# untitled.net
KiCad netlist of a schematic drawn in EAGLE
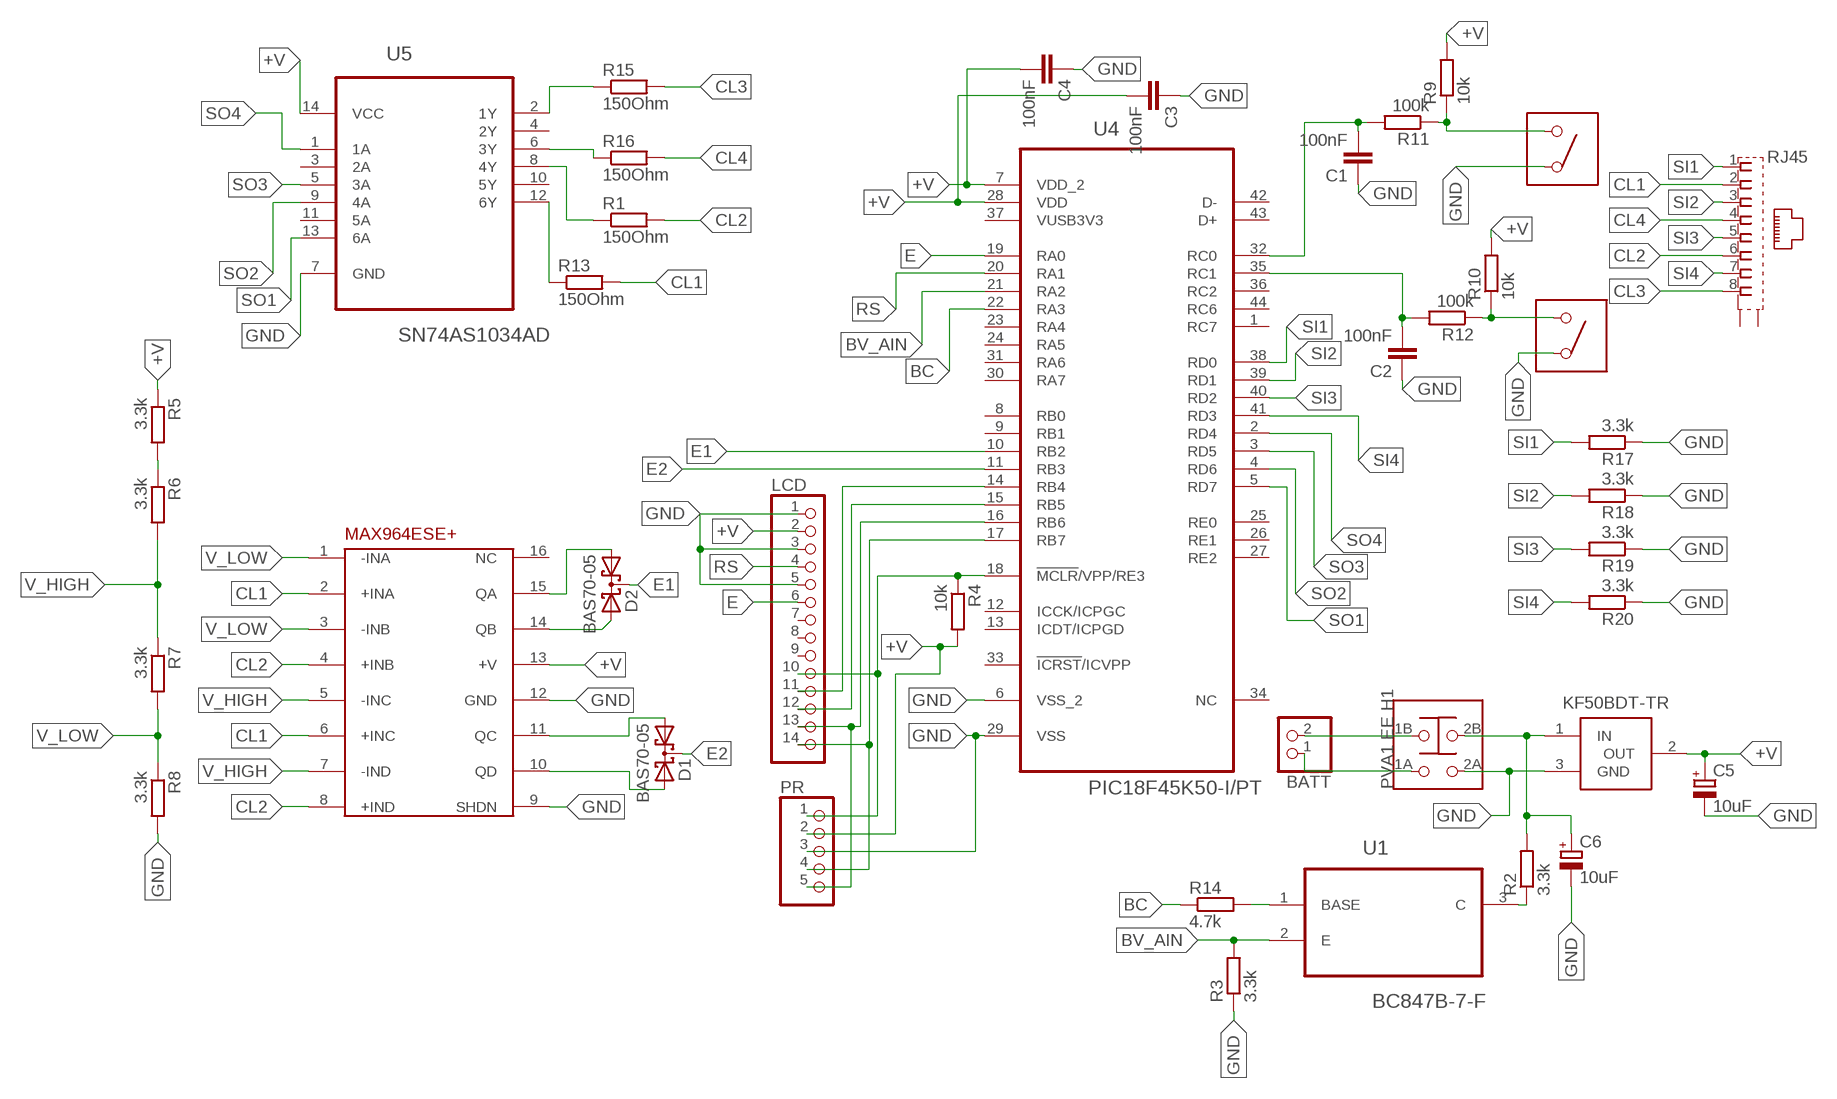
[diagram p0: schematic, sheet 1]

(export (version "E")
  (design (tool "Eeschema 10.0.6"))
  (components
    (comp (ref "BATT")
      (value "PINHD-1X2")
      (footprint "eagle-import:1X02")
      (libsource (lib "eagle-import") (part "PINHD-1X2"))
    )
    (comp (ref "C1")
      (value "100nF")
      (footprint "eagle-import:C0603")
      (fields (field (name "MF") "YAGEO (PHYCOMP)") (field (name "MPN") "CC0603KRX7R7BB104"))
      (libsource (lib "eagle-import") (part "C-EUC0603"))
    )
    (comp (ref "C2")
      (value "100nF")
      (footprint "eagle-import:C0603")
      (fields (field (name "MF") "YAGEO (PHYCOMP)") (field (name "MPN") "CC0603KRX7R7BB104"))
      (libsource (lib "eagle-import") (part "C-EUC0603"))
    )
    (comp (ref "C3")
      (value "100nF")
      (footprint "eagle-import:C0603")
      (fields (field (name "MF") "YAGEO (PHYCOMP)") (field (name "MPN") "CC0603KRX7R7BB104"))
      (libsource (lib "eagle-import") (part "C-EUC0603"))
    )
    (comp (ref "C4")
      (value "100nF")
      (footprint "eagle-import:C0603")
      (fields (field (name "MF") "YAGEO (PHYCOMP)") (field (name "MPN") "CC0603KRX7R7BB104"))
      (libsource (lib "eagle-import") (part "C-EUC0603"))
    )
    (comp (ref "C5")
      (value "10uF")
      (footprint "eagle-import:153CLV-0405")
      (fields (field (name "MF") "RUBYCON") (field (name "MPN") "16TZV10M4X6.1"))
      (libsource (lib "eagle-import") (part "CPOL-EU153CLV-0405"))
    )
    (comp (ref "C6")
      (value "10uF")
      (footprint "eagle-import:153CLV-0405")
      (fields (field (name "MF") "RUBYCON") (field (name "MPN") "16TZV10M4X6.1"))
      (libsource (lib "eagle-import") (part "CPOL-EU153CLV-0405"))
    )
    (comp (ref "D1")
      (value "BAS70-05")
      (footprint "eagle-import:SOT23")
      (libsource (lib "eagle-import") (part "BAS70-05"))
    )
    (comp (ref "D2")
      (value "BAS70-05")
      (footprint "eagle-import:SOT23")
      (libsource (lib "eagle-import") (part "BAS70-05"))
    )
    (comp (ref "LCD")
      (value "PINHD-1X14")
      (footprint "eagle-import:1X14")
      (libsource (lib "eagle-import") (part "PINHD-1X14"))
    )
    (comp (ref "PR")
      (value "PINHD-1X5")
      (footprint "eagle-import:1X05")
      (libsource (lib "eagle-import") (part "PINHD-1X5"))
    )
    (comp (ref "R1")
      (value "150Ohm")
      (footprint "eagle-import:R0603")
      (fields (field (name "MF") "TE CONNECTIVITY / NEOHM") (field (name "MPN") "CPF0603F150RC1"))
      (libsource (lib "eagle-import") (part "R-EU_R0603"))
    )
    (comp (ref "R2")
      (value "3.3k")
      (footprint "eagle-import:R0603")
      (fields (field (name "MF") "TE CONNECTIVITY") (field (name "MPN") "CRGH0603F3K3"))
      (libsource (lib "eagle-import") (part "R-EU_R0603"))
    )
    (comp (ref "R3")
      (value "3.3k")
      (footprint "eagle-import:R0603")
      (fields (field (name "MF") "TE CONNECTIVITY") (field (name "MPN") "CRGH0603F3K3"))
      (libsource (lib "eagle-import") (part "R-EU_R0603"))
    )
    (comp (ref "R4")
      (value "10k")
      (footprint "eagle-import:R0603")
      (fields (field (name "MF") "VISHAY") (field (name "MPN") "CRCW060310K0FKTA"))
      (libsource (lib "eagle-import") (part "R-EU_R0603"))
    )
    (comp (ref "R5")
      (value "3.3k")
      (footprint "eagle-import:R0603")
      (fields (field (name "MF") "TE CONNECTIVITY") (field (name "MPN") "CRGH0603F3K3"))
      (libsource (lib "eagle-import") (part "R-EU_R0603"))
    )
    (comp (ref "R6")
      (value "3.3k")
      (footprint "eagle-import:R0603")
      (fields (field (name "MF") "TE CONNECTIVITY") (field (name "MPN") "CRGH0603F3K3"))
      (libsource (lib "eagle-import") (part "R-EU_R0603"))
    )
    (comp (ref "R7")
      (value "3.3k")
      (footprint "eagle-import:R0603")
      (fields (field (name "MF") "TE CONNECTIVITY") (field (name "MPN") "CRGH0603F3K3"))
      (libsource (lib "eagle-import") (part "R-EU_R0603"))
    )
    (comp (ref "R8")
      (value "3.3k")
      (footprint "eagle-import:R0603")
      (fields (field (name "MF") "TE CONNECTIVITY") (field (name "MPN") "CRGH0603F3K3"))
      (libsource (lib "eagle-import") (part "R-EU_R0603"))
    )
    (comp (ref "R9")
      (value "10k")
      (footprint "eagle-import:R0603")
      (fields (field (name "MF") "VISHAY") (field (name "MPN") "CRCW060310K0FKTA"))
      (libsource (lib "eagle-import") (part "R-EU_R0603"))
    )
    (comp (ref "R10")
      (value "10k")
      (footprint "eagle-import:R0603")
      (fields (field (name "MF") "VISHAY") (field (name "MPN") "CRCW060310K0FKTA"))
      (libsource (lib "eagle-import") (part "R-EU_R0603"))
    )
    (comp (ref "R11")
      (value "100k")
      (footprint "eagle-import:R0603")
      (fields (field (name "MF") "TE CONNECTIVITY") (field (name "MPN") "CRGH0603J100K"))
      (libsource (lib "eagle-import") (part "R-EU_R0603"))
    )
    (comp (ref "R12")
      (value "100k")
      (footprint "eagle-import:R0603")
      (fields (field (name "MF") "TE CONNECTIVITY") (field (name "MPN") "CRGH0603J100K"))
      (libsource (lib "eagle-import") (part "R-EU_R0603"))
    )
    (comp (ref "R13")
      (value "150Ohm")
      (footprint "eagle-import:R0603")
      (fields (field (name "MF") "TE CONNECTIVITY / NEOHM") (field (name "MPN") "CPF0603F150RC1"))
      (libsource (lib "eagle-import") (part "R-EU_R0603"))
    )
    (comp (ref "R14")
      (value "4.7k")
      (footprint "eagle-import:R0603")
      (fields (field (name "MF") "VISHAY") (field (name "MPN") "CRCW06034K70FKEA"))
      (libsource (lib "eagle-import") (part "R-EU_R0603"))
    )
    (comp (ref "R15")
      (value "150Ohm")
      (footprint "eagle-import:R0603")
      (fields (field (name "MF") "TE CONNECTIVITY / NEOHM") (field (name "MPN") "CPF0603F150RC1"))
      (libsource (lib "eagle-import") (part "R-EU_R0603"))
    )
    (comp (ref "R16")
      (value "150Ohm")
      (footprint "eagle-import:R0603")
      (fields (field (name "MF") "TE CONNECTIVITY / NEOHM") (field (name "MPN") "CPF0603F150RC1"))
      (libsource (lib "eagle-import") (part "R-EU_R0603"))
    )
    (comp (ref "R17")
      (value "3.3k")
      (footprint "eagle-import:R0603")
      (fields (field (name "MF") "TE CONNECTIVITY") (field (name "MPN") "CRGH0603F3K3"))
      (libsource (lib "eagle-import") (part "R-EU_R0603"))
    )
    (comp (ref "R18")
      (value "3.3k")
      (footprint "eagle-import:R0603")
      (fields (field (name "MF") "TE CONNECTIVITY") (field (name "MPN") "CRGH0603F3K3"))
      (libsource (lib "eagle-import") (part "R-EU_R0603"))
    )
    (comp (ref "R19")
      (value "3.3k")
      (footprint "eagle-import:R0603")
      (fields (field (name "MF") "TE CONNECTIVITY") (field (name "MPN") "CRGH0603F3K3"))
      (libsource (lib "eagle-import") (part "R-EU_R0603"))
    )
    (comp (ref "R20")
      (value "3.3k")
      (footprint "eagle-import:R0603")
      (fields (field (name "MF") "TE CONNECTIVITY") (field (name "MPN") "CRGH0603F3K3"))
      (libsource (lib "eagle-import") (part "R-EU_R0603"))
    )
    (comp (ref "RJ45")
      (value "1-406541-6")
      (footprint "eagle-import:RJ45")
      (fields (field (name "MF") "TE CONNECTIVITY / AMP") (field (name "MF_1") "AMP - TE CONNECTIVITY"))
      (libsource (lib "eagle-import") (part "1-406541-6"))
    )
    (comp (ref "U$1")
      (value "KF50BDT-TR")
      (footprint "eagle-import:TO252")
      (fields (field (name "MF") "STMICROELECTRONICS"))
      (libsource (lib "eagle-import") (part "KF50BDT-TR"))
    )
    (comp (ref "U$2")
      (value "MAX964ESE+")
      (footprint "eagle-import:SO16")
      (fields
        (field (name "MF") "MAXIM INTEGRATED PRODUCTS")
        (field (name "MPN") "MAX9201ESE+")
        (field (name "MPN_1") "MAX964ESE+")
        (field (name "OC_FARNELL") "2518928")
      )
      (libsource (lib "eagle-import") (part "MAX964ESE+"))
    )
    (comp (ref "U$3")
      (value "PVA1_EE_H1")
      (footprint "eagle-import:PVA1_EE_H1")
      (fields (field (name "MF") "C & K COMPONENTS") (field (name "MPN") "PVA1 EE H1 3.5N V2"))
      (libsource (lib "eagle-import") (part "PVA1_EE_H1"))
    )
    (comp (ref "U$4")
      (value "FSM4JRT")
      (footprint "eagle-import:FSM4JRT")
      (fields
        (field (name "MPN") "TE CONNECTIVITY / ALCOSWITCH")
        (field (name "MF") "TE CONNECTIVITY / ALCOSWITCH")
        (field (name "MPN_1") "FSM4JRT")
      )
      (libsource (lib "eagle-import") (part "FSM4JRT"))
    )
    (comp (ref "U$5")
      (value "FSM4JRT")
      (footprint "eagle-import:FSM4JRT")
      (fields
        (field (name "MPN") "TE CONNECTIVITY / ALCOSWITCH")
        (field (name "MF") "TE CONNECTIVITY / ALCOSWITCH")
        (field (name "MPN_1") "FSM4JRT")
      )
      (libsource (lib "eagle-import") (part "FSM4JRT"))
    )
    (comp (ref "U1")
      (value "BC847B-7-F")
      (footprint "eagle-import:SOT95P240X110-3N")
      (fields (field (name "MF") "DIODES INC."))
      (libsource (lib "eagle-import") (part "BC847B-7-F"))
    )
    (comp (ref "U4")
      (value "PIC18F45K50-I/PT")
      (footprint "eagle-import:TQFP80P1200X1200X120-44N")
      (fields (field (name "MF") "MICROCHIP"))
      (libsource (lib "eagle-import") (part "PIC18F45K50-I/PT"))
    )
    (comp (ref "U5")
      (value "SN74AS1034AD")
      (footprint "eagle-import:SOIC127P600X175-14N")
      (fields (field (name "MF") "TEXAS INSTRUMENTS"))
      (libsource (lib "eagle-import") (part "SN74AS1034AD"))
    )
  )
  (nets
    (net (code "1") (name "+V") (class "Default")
      (node (ref "C3") (pin "2") (pinfunction "2_2") (pintype "passive"))
      (node (ref "C4") (pin "2") (pinfunction "2_2") (pintype "passive"))
      (node (ref "C5") (pin "+") (pinfunction "+_+") (pintype "passive"))
      (node (ref "LCD") (pin "2") (pinfunction "2_2") (pintype "passive"))
      (node (ref "PR") (pin "2") (pinfunction "2_2") (pintype "passive"))
      (node (ref "R10") (pin "2") (pinfunction "2_2") (pintype "passive"))
      (node (ref "R4") (pin "2") (pinfunction "2_2") (pintype "passive"))
      (node (ref "R5") (pin "1") (pinfunction "1_1") (pintype "passive"))
      (node (ref "R9") (pin "2") (pinfunction "2_2") (pintype "passive"))
      (node (ref "U$1") (pin "2") (pinfunction "OUT_2") (pintype "output"))
      (node (ref "U$2") (pin "13") (pinfunction "+V_13") (pintype "power_in"))
      (node (ref "U4") (pin "28") (pinfunction "VDD_28") (pintype "power_in"))
      (node (ref "U4") (pin "7") (pinfunction "VDD_2_7") (pintype "power_in"))
      (node (ref "U5") (pin "14") (pinfunction "VCC_14") (pintype "power_in"))
    )
    (net (code "2") (name "/VUSB3V3") (class "Default")
      (node (ref "U4") (pin "37") (pinfunction "VUSB3V3_37") (pintype "power_in"))
    )
    (net (code "3") (name "BC") (class "Default")
      (node (ref "R14") (pin "1") (pinfunction "1_1") (pintype "passive"))
      (node (ref "U4") (pin "22") (pinfunction "RA3_22") (pintype "bidirectional"))
    )
    (net (code "4") (name "BV_AIN") (class "Default")
      (node (ref "R3") (pin "2") (pinfunction "2_2") (pintype "passive"))
      (node (ref "U1") (pin "2") (pinfunction "E_2") (pintype "passive"))
      (node (ref "U4") (pin "21") (pinfunction "RA2_21") (pintype "bidirectional"))
    )
    (net (code "5") (name "CL1") (class "Default")
      (node (ref "R13") (pin "2") (pinfunction "2_2") (pintype "passive"))
      (node (ref "RJ45") (pin "2") (pinfunction "2_2") (pintype "passive"))
      (node (ref "U$2") (pin "2") (pinfunction "+INA_2") (pintype "input"))
      (node (ref "U$2") (pin "6") (pinfunction "+INC_6") (pintype "input"))
    )
    (net (code "6") (name "CL2") (class "Default")
      (node (ref "R1") (pin "2") (pinfunction "2_2") (pintype "passive"))
      (node (ref "RJ45") (pin "6") (pinfunction "6_6") (pintype "passive"))
      (node (ref "U$2") (pin "4") (pinfunction "+INB_4") (pintype "input"))
      (node (ref "U$2") (pin "8") (pinfunction "+IND_8") (pintype "input"))
    )
    (net (code "7") (name "CL3") (class "Default")
      (node (ref "R15") (pin "2") (pinfunction "2_2") (pintype "passive"))
      (node (ref "RJ45") (pin "8") (pinfunction "8_8") (pintype "passive"))
    )
    (net (code "8") (name "CL4") (class "Default")
      (node (ref "R16") (pin "2") (pinfunction "2_2") (pintype "passive"))
      (node (ref "RJ45") (pin "4") (pinfunction "4_4") (pintype "passive"))
    )
    (net (code "9") (name "E") (class "Default")
      (node (ref "LCD") (pin "6") (pinfunction "6_6") (pintype "passive"))
      (node (ref "U4") (pin "19") (pinfunction "RA0_19") (pintype "bidirectional"))
    )
    (net (code "10") (name "E1") (class "Default")
      (node (ref "D2") (pin "3") (pinfunction "C_3") (pintype "passive"))
      (node (ref "U4") (pin "10") (pinfunction "RB2_10") (pintype "bidirectional"))
    )
    (net (code "11") (name "E2") (class "Default")
      (node (ref "D1") (pin "3") (pinfunction "C_3") (pintype "passive"))
      (node (ref "U4") (pin "11") (pinfunction "RB3_11") (pintype "bidirectional"))
    )
    (net (code "12") (name "GND") (class "Default")
      (node (ref "C1") (pin "1") (pinfunction "1_1") (pintype "passive"))
      (node (ref "C2") (pin "1") (pinfunction "1_1") (pintype "passive"))
      (node (ref "C3") (pin "1") (pinfunction "1_1") (pintype "passive"))
      (node (ref "C4") (pin "1") (pinfunction "1_1") (pintype "passive"))
      (node (ref "C5") (pin "-") (pinfunction "-_-") (pintype "passive"))
      (node (ref "C6") (pin "-") (pinfunction "-_-") (pintype "passive"))
      (node (ref "LCD") (pin "1") (pinfunction "1_1") (pintype "passive"))
      (node (ref "LCD") (pin "3") (pinfunction "3_3") (pintype "passive"))
      (node (ref "LCD") (pin "5") (pinfunction "5_5") (pintype "passive"))
      (node (ref "PR") (pin "3") (pinfunction "3_3") (pintype "passive"))
      (node (ref "R17") (pin "1") (pinfunction "1_1") (pintype "passive"))
      (node (ref "R18") (pin "1") (pinfunction "1_1") (pintype "passive"))
      (node (ref "R19") (pin "1") (pinfunction "1_1") (pintype "passive"))
      (node (ref "R20") (pin "1") (pinfunction "1_1") (pintype "passive"))
      (node (ref "R3") (pin "1") (pinfunction "1_1") (pintype "passive"))
      (node (ref "R8") (pin "2") (pinfunction "2_2") (pintype "passive"))
      (node (ref "U$1") (pin "3") (pinfunction "GND_3") (pintype "output"))
      (node (ref "U$2") (pin "12") (pinfunction "GND_12") (pintype "power_in"))
      (node (ref "U$2") (pin "9") (pinfunction "SHDN_9") (pintype "input"))
      (node (ref "U$3") (pin "2A") (pinfunction "2A_2A") (pintype "bidirectional"))
      (node (ref "U$4") (pin "2") (pinfunction "2_2") (pintype "passive"))
      (node (ref "U$5") (pin "2") (pinfunction "2_2") (pintype "passive"))
      (node (ref "U4") (pin "29") (pinfunction "VSS_29") (pintype "power_in"))
      (node (ref "U4") (pin "6") (pinfunction "VSS_2_6") (pintype "power_in"))
      (node (ref "U5") (pin "7") (pinfunction "GND_7") (pintype "passive"))
    )
    (net (code "13") (name "Net-(BATT-Pad1)") (class "Default")
      (node (ref "BATT") (pin "1") (pinfunction "1_1") (pintype "passive"))
      (node (ref "U$3") (pin "1A") (pinfunction "1A_1A") (pintype "bidirectional"))
    )
    (net (code "14") (name "Net-(BATT-Pad2)") (class "Default")
      (node (ref "BATT") (pin "2") (pinfunction "2_2") (pintype "passive"))
      (node (ref "U$3") (pin "1B") (pinfunction "1B_1B") (pintype "bidirectional"))
    )
    (net (code "15") (name "Net-(D1-A1)") (class "Default")
      (node (ref "D1") (pin "1") (pinfunction "A1_1") (pintype "passive"))
      (node (ref "U$2") (pin "11") (pinfunction "QC_11") (pintype "output"))
    )
    (net (code "16") (name "Net-(D1-A2)") (class "Default")
      (node (ref "D1") (pin "2") (pinfunction "A2_2") (pintype "passive"))
      (node (ref "U$2") (pin "10") (pinfunction "QD_10") (pintype "output"))
    )
    (net (code "17") (name "Net-(D2-A1)") (class "Default")
      (node (ref "D2") (pin "1") (pinfunction "A1_1") (pintype "passive"))
      (node (ref "U$2") (pin "15") (pinfunction "QA_15") (pintype "output"))
    )
    (net (code "18") (name "Net-(D2-A2)") (class "Default")
      (node (ref "D2") (pin "2") (pinfunction "A2_2") (pintype "passive"))
      (node (ref "U$2") (pin "14") (pinfunction "QB_14") (pintype "output"))
    )
    (net (code "19") (name "Net-(R5-Pad2)") (class "Default")
      (node (ref "R5") (pin "2") (pinfunction "2_2") (pintype "passive"))
      (node (ref "R6") (pin "1") (pinfunction "1_1") (pintype "passive"))
    )
    (net (code "20") (name "Net-(R10-Pad1)") (class "Default")
      (node (ref "R10") (pin "1") (pinfunction "1_1") (pintype "passive"))
      (node (ref "R12") (pin "1") (pinfunction "1_1") (pintype "passive"))
      (node (ref "U$5") (pin "1") (pinfunction "1_1") (pintype "passive"))
    )
    (net (code "21") (name "Net-(R11-Pad1)") (class "Default")
      (node (ref "R11") (pin "1") (pinfunction "1_1") (pintype "passive"))
      (node (ref "R9") (pin "1") (pinfunction "1_1") (pintype "passive"))
      (node (ref "U$4") (pin "1") (pinfunction "1_1") (pintype "passive"))
    )
    (net (code "22") (name "Net-(U$1-IN)") (class "Default")
      (node (ref "C6") (pin "+") (pinfunction "+_+") (pintype "passive"))
      (node (ref "R2") (pin "2") (pinfunction "2_2") (pintype "passive"))
      (node (ref "U$1") (pin "1") (pinfunction "IN_1") (pintype "input"))
      (node (ref "U$3") (pin "2B") (pinfunction "2B_2B") (pintype "bidirectional"))
    )
    (net (code "23") (name "Net-(U1-BASE)") (class "Default")
      (node (ref "R14") (pin "2") (pinfunction "2_2") (pintype "passive"))
      (node (ref "U1") (pin "1") (pinfunction "BASE_1") (pintype "passive"))
    )
    (net (code "24") (name "Net-(U1-C)") (class "Default")
      (node (ref "R2") (pin "1") (pinfunction "1_1") (pintype "passive"))
      (node (ref "U1") (pin "3") (pinfunction "C_3") (pintype "passive"))
    )
    (net (code "25") (name "Net-(U4-RB4)") (class "Default")
      (node (ref "LCD") (pin "11") (pinfunction "11_11") (pintype "passive"))
      (node (ref "U4") (pin "14") (pinfunction "RB4_14") (pintype "bidirectional"))
    )
    (net (code "26") (name "Net-(U4-RB5)") (class "Default")
      (node (ref "LCD") (pin "12") (pinfunction "12_12") (pintype "passive"))
      (node (ref "U4") (pin "15") (pinfunction "RB5_15") (pintype "bidirectional"))
    )
    (net (code "27") (name "Net-(U4-RB6)") (class "Default")
      (node (ref "LCD") (pin "13") (pinfunction "13_13") (pintype "passive"))
      (node (ref "PR") (pin "5") (pinfunction "5_5") (pintype "passive"))
      (node (ref "U4") (pin "16") (pinfunction "RB6_16") (pintype "bidirectional"))
    )
    (net (code "28") (name "Net-(U4-RB7)") (class "Default")
      (node (ref "LCD") (pin "14") (pinfunction "14_14") (pintype "passive"))
      (node (ref "PR") (pin "4") (pinfunction "4_4") (pintype "passive"))
      (node (ref "U4") (pin "17") (pinfunction "RB7_17") (pintype "bidirectional"))
    )
    (net (code "29") (name "Net-(U4-RC0)") (class "Default")
      (node (ref "C1") (pin "2") (pinfunction "2_2") (pintype "passive"))
      (node (ref "R11") (pin "2") (pinfunction "2_2") (pintype "passive"))
      (node (ref "U4") (pin "32") (pinfunction "RC0_32") (pintype "bidirectional"))
    )
    (net (code "30") (name "Net-(U4-RC1)") (class "Default")
      (node (ref "C2") (pin "2") (pinfunction "2_2") (pintype "passive"))
      (node (ref "R12") (pin "2") (pinfunction "2_2") (pintype "passive"))
      (node (ref "U4") (pin "35") (pinfunction "RC1_35") (pintype "bidirectional"))
    )
    (net (code "31") (name "Net-(U4-~{MCLR}{slash}VPP{slash}RE3)") (class "Default")
      (node (ref "LCD") (pin "10") (pinfunction "10_10") (pintype "passive"))
      (node (ref "PR") (pin "1") (pinfunction "1_1") (pintype "passive"))
      (node (ref "R4") (pin "1") (pinfunction "1_1") (pintype "passive"))
      (node (ref "U4") (pin "18") (pinfunction "~{MCLR}/VPP/RE3_18") (pintype "input"))
    )
    (net (code "32") (name "Net-(U5-1Y)") (class "Default")
      (node (ref "R15") (pin "1") (pinfunction "1_1") (pintype "passive"))
      (node (ref "U5") (pin "2") (pinfunction "1Y_2") (pintype "output"))
    )
    (net (code "33") (name "Net-(U5-3Y)") (class "Default")
      (node (ref "R16") (pin "1") (pinfunction "1_1") (pintype "passive"))
      (node (ref "U5") (pin "6") (pinfunction "3Y_6") (pintype "output"))
    )
    (net (code "34") (name "Net-(U5-4Y)") (class "Default")
      (node (ref "R1") (pin "1") (pinfunction "1_1") (pintype "passive"))
      (node (ref "U5") (pin "8") (pinfunction "4Y_8") (pintype "output"))
    )
    (net (code "35") (name "Net-(U5-6Y)") (class "Default")
      (node (ref "R13") (pin "1") (pinfunction "1_1") (pintype "passive"))
      (node (ref "U5") (pin "12") (pinfunction "6Y_12") (pintype "output"))
    )
    (net (code "36") (name "RS") (class "Default")
      (node (ref "LCD") (pin "4") (pinfunction "4_4") (pintype "passive"))
      (node (ref "U4") (pin "20") (pinfunction "RA1_20") (pintype "bidirectional"))
    )
    (net (code "37") (name "SI1") (class "Default")
      (node (ref "R17") (pin "2") (pinfunction "2_2") (pintype "passive"))
      (node (ref "RJ45") (pin "1") (pinfunction "1_1") (pintype "passive"))
      (node (ref "U4") (pin "38") (pinfunction "RD0_38") (pintype "bidirectional"))
    )
    (net (code "38") (name "SI2") (class "Default")
      (node (ref "R18") (pin "2") (pinfunction "2_2") (pintype "passive"))
      (node (ref "RJ45") (pin "3") (pinfunction "3_3") (pintype "passive"))
      (node (ref "U4") (pin "39") (pinfunction "RD1_39") (pintype "bidirectional"))
    )
    (net (code "39") (name "SI3") (class "Default")
      (node (ref "R19") (pin "2") (pinfunction "2_2") (pintype "passive"))
      (node (ref "RJ45") (pin "5") (pinfunction "5_5") (pintype "passive"))
      (node (ref "U4") (pin "40") (pinfunction "RD2_40") (pintype "bidirectional"))
    )
    (net (code "40") (name "SI4") (class "Default")
      (node (ref "R20") (pin "2") (pinfunction "2_2") (pintype "passive"))
      (node (ref "RJ45") (pin "7") (pinfunction "7_7") (pintype "passive"))
      (node (ref "U4") (pin "41") (pinfunction "RD3_41") (pintype "bidirectional"))
    )
    (net (code "41") (name "SO1") (class "Default")
      (node (ref "U4") (pin "5") (pinfunction "RD7_5") (pintype "bidirectional"))
      (node (ref "U5") (pin "13") (pinfunction "6A_13") (pintype "input"))
    )
    (net (code "42") (name "SO2") (class "Default")
      (node (ref "U4") (pin "4") (pinfunction "RD6_4") (pintype "bidirectional"))
      (node (ref "U5") (pin "9") (pinfunction "4A_9") (pintype "input"))
    )
    (net (code "43") (name "SO3") (class "Default")
      (node (ref "U4") (pin "3") (pinfunction "RD5_3") (pintype "bidirectional"))
      (node (ref "U5") (pin "5") (pinfunction "3A_5") (pintype "input"))
    )
    (net (code "44") (name "SO4") (class "Default")
      (node (ref "U4") (pin "2") (pinfunction "RD4_2") (pintype "bidirectional"))
      (node (ref "U5") (pin "1") (pinfunction "1A_1") (pintype "input"))
    )
    (net (code "45") (name "V_HIGH") (class "Default")
      (node (ref "R6") (pin "2") (pinfunction "2_2") (pintype "passive"))
      (node (ref "R7") (pin "1") (pinfunction "1_1") (pintype "passive"))
      (node (ref "U$2") (pin "5") (pinfunction "-INC_5") (pintype "input"))
      (node (ref "U$2") (pin "7") (pinfunction "-IND_7") (pintype "input"))
    )
    (net (code "46") (name "V_LOW") (class "Default")
      (node (ref "R7") (pin "2") (pinfunction "2_2") (pintype "passive"))
      (node (ref "R8") (pin "1") (pinfunction "1_1") (pintype "passive"))
      (node (ref "U$2") (pin "1") (pinfunction "-INA_1") (pintype "input"))
      (node (ref "U$2") (pin "3") (pinfunction "-INB_3") (pintype "input"))
    )
    (net (code "47") (name "unconnected-(LCD-Pad7)") (class "Default")
      (node (ref "LCD") (pin "7") (pinfunction "7_7") (pintype "passive"))
    )
    (net (code "48") (name "unconnected-(LCD-Pad8)") (class "Default")
      (node (ref "LCD") (pin "8") (pinfunction "8_8") (pintype "passive"))
    )
    (net (code "49") (name "unconnected-(LCD-Pad9)") (class "Default")
      (node (ref "LCD") (pin "9") (pinfunction "9_9") (pintype "passive"))
    )
    (net (code "50") (name "unconnected-(RJ45-PadS1)") (class "Default")
      (node (ref "RJ45") (pin "S1") (pinfunction "S1_S1") (pintype "passive"))
    )
    (net (code "51") (name "unconnected-(RJ45-PadS2)") (class "Default")
      (node (ref "RJ45") (pin "S2") (pinfunction "S2_S2") (pintype "passive"))
    )
    (net (code "52") (name "unconnected-(U$2-NC-Pad16)") (class "Default")
      (node (ref "U$2") (pin "16") (pinfunction "NC_16") (pintype "no_connect"))
    )
    (net (code "53") (name "unconnected-(U4-D+-Pad43)") (class "Default")
      (node (ref "U4") (pin "43") (pinfunction "D+_43") (pintype "passive"))
    )
    (net (code "54") (name "unconnected-(U4-D--Pad42)") (class "Default")
      (node (ref "U4") (pin "42") (pinfunction "D-_42") (pintype "passive"))
    )
    (net (code "55") (name "unconnected-(U4-ICCK{slash}ICPGC-Pad12)") (class "Default")
      (node (ref "U4") (pin "12") (pinfunction "ICCK/ICPGC_12") (pintype "passive"))
    )
    (net (code "56") (name "unconnected-(U4-ICDT{slash}ICPGD-Pad13)") (class "Default")
      (node (ref "U4") (pin "13") (pinfunction "ICDT/ICPGD_13") (pintype "passive"))
    )
    (net (code "57") (name "unconnected-(U4-NC-Pad34)") (class "Default")
      (node (ref "U4") (pin "34") (pinfunction "NC_34") (pintype "passive"))
    )
    (net (code "58") (name "unconnected-(U4-RA4-Pad23)") (class "Default")
      (node (ref "U4") (pin "23") (pinfunction "RA4_23") (pintype "bidirectional"))
    )
    (net (code "59") (name "unconnected-(U4-RA5-Pad24)") (class "Default")
      (node (ref "U4") (pin "24") (pinfunction "RA5_24") (pintype "bidirectional"))
    )
    (net (code "60") (name "unconnected-(U4-RA6-Pad31)") (class "Default")
      (node (ref "U4") (pin "31") (pinfunction "RA6_31") (pintype "bidirectional"))
    )
    (net (code "61") (name "unconnected-(U4-RA7-Pad30)") (class "Default")
      (node (ref "U4") (pin "30") (pinfunction "RA7_30") (pintype "bidirectional"))
    )
    (net (code "62") (name "unconnected-(U4-RB0-Pad8)") (class "Default")
      (node (ref "U4") (pin "8") (pinfunction "RB0_8") (pintype "bidirectional"))
    )
    (net (code "63") (name "unconnected-(U4-RB1-Pad9)") (class "Default")
      (node (ref "U4") (pin "9") (pinfunction "RB1_9") (pintype "bidirectional"))
    )
    (net (code "64") (name "unconnected-(U4-RC2-Pad36)") (class "Default")
      (node (ref "U4") (pin "36") (pinfunction "RC2_36") (pintype "bidirectional"))
    )
    (net (code "65") (name "unconnected-(U4-RC6-Pad44)") (class "Default")
      (node (ref "U4") (pin "44") (pinfunction "RC6_44") (pintype "bidirectional"))
    )
    (net (code "66") (name "unconnected-(U4-RC7-Pad1)") (class "Default")
      (node (ref "U4") (pin "1") (pinfunction "RC7_1") (pintype "bidirectional"))
    )
    (net (code "67") (name "unconnected-(U4-RE0-Pad25)") (class "Default")
      (node (ref "U4") (pin "25") (pinfunction "RE0_25") (pintype "bidirectional"))
    )
    (net (code "68") (name "unconnected-(U4-RE1-Pad26)") (class "Default")
      (node (ref "U4") (pin "26") (pinfunction "RE1_26") (pintype "bidirectional"))
    )
    (net (code "69") (name "unconnected-(U4-RE2-Pad27)") (class "Default")
      (node (ref "U4") (pin "27") (pinfunction "RE2_27") (pintype "bidirectional"))
    )
    (net (code "70") (name "unconnected-(U4-~{ICRST}{slash}ICVPP-Pad33)") (class "Default")
      (node (ref "U4") (pin "33") (pinfunction "~{ICRST}/ICVPP_33") (pintype "passive"))
    )
    (net (code "71") (name "unconnected-(U5-2A-Pad3)") (class "Default")
      (node (ref "U5") (pin "3") (pinfunction "2A_3") (pintype "input"))
    )
    (net (code "72") (name "unconnected-(U5-2Y-Pad4)") (class "Default")
      (node (ref "U5") (pin "4") (pinfunction "2Y_4") (pintype "output"))
    )
    (net (code "73") (name "unconnected-(U5-5A-Pad11)") (class "Default")
      (node (ref "U5") (pin "11") (pinfunction "5A_11") (pintype "input"))
    )
    (net (code "74") (name "unconnected-(U5-5Y-Pad10)") (class "Default")
      (node (ref "U5") (pin "10") (pinfunction "5Y_10") (pintype "output"))
    )
  )
)
